# FMCio_rowsEFJK.net
KiCad netlist of a schematic drawn in Altium Designer
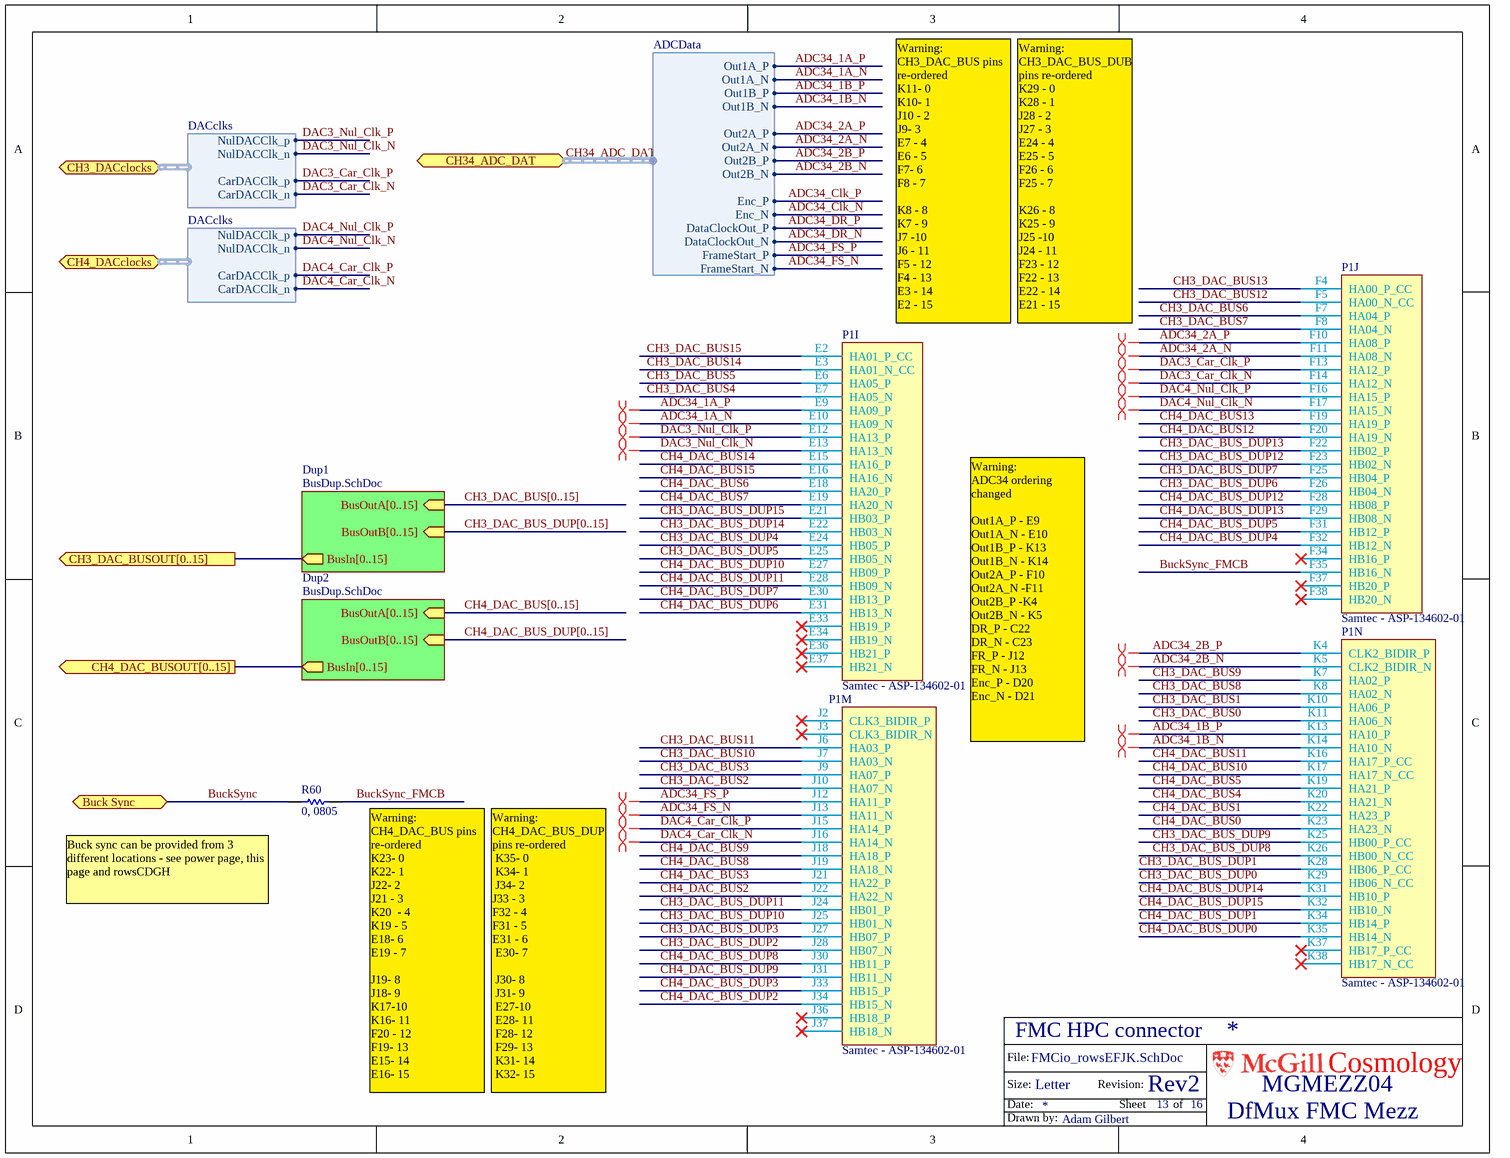
[diagram p0: FMCio_rowsEFJK.SchDoc]

(export (version "E")
  (design (tool "Eeschema 10.0.6"))
  (components
    (comp (ref "P1")
      (value "Samtec - ASP-134602-01")
      (footprint "BTB-SM1-27-2V400M")
      (description "Samtec ASP-134602-01")
      (fields (field (name "MANUFACTURER") "Samtec"))
      (libsource (lib "AdamsParts") (part "Samtec - ASP-134602-01"))
    )
    (comp (ref "R60")
      (value "0, 0805")
      (footprint "0805")
      (description "RES 0.0 OHM 1/8W 0805 SMD")
      (fields (field (name "MANUFACTURER") "e.g Vishay/Dale"))
      (libsource (lib "AdamsParts") (part "Res1812"))
    )
  )
  (nets
    (net (code "35") (name "/ADC34_1A_N") (class "Default")
      (node (ref "P1") (pin "E10") (pinfunction "HA09_N_E10") (pintype "passive"))
    )
    (net (code "36") (name "/ADC34_1A_P") (class "Default")
      (node (ref "P1") (pin "E9") (pinfunction "HA09_P_E9") (pintype "passive"))
    )
    (net (code "37") (name "/ADC34_1B_N") (class "Default")
      (node (ref "P1") (pin "K14") (pinfunction "HA10_N_K14") (pintype "passive"))
    )
    (net (code "38") (name "/ADC34_1B_P") (class "Default")
      (node (ref "P1") (pin "K13") (pinfunction "HA10_P_K13") (pintype "passive"))
    )
    (net (code "39") (name "/ADC34_2A_N") (class "Default")
      (node (ref "P1") (pin "F11") (pinfunction "HA08_N_F11") (pintype "passive"))
    )
    (net (code "40") (name "/ADC34_2A_P") (class "Default")
      (node (ref "P1") (pin "F10") (pinfunction "HA08_P_F10") (pintype "passive"))
    )
    (net (code "41") (name "/ADC34_2B_N") (class "Default")
      (node (ref "P1") (pin "K5") (pinfunction "CLK2_BIDIR_N_K5") (pintype "passive"))
    )
    (net (code "42") (name "/ADC34_2B_P") (class "Default")
      (node (ref "P1") (pin "K4") (pinfunction "CLK2_BIDIR_P_K4") (pintype "passive"))
    )
    (net (code "47") (name "/ADC34_FS_N") (class "Default")
      (node (ref "P1") (pin "J13") (pinfunction "HA11_N_J13") (pintype "passive"))
    )
    (net (code "48") (name "/ADC34_FS_P") (class "Default")
      (node (ref "P1") (pin "J12") (pinfunction "HA11_P_J12") (pintype "passive"))
    )
    (net (code "49") (name "/BuckSync") (class "Default")
      (node (ref "R60") (pin "2") (pinfunction "2_2") (pintype "passive"))
    )
    (net (code "50") (name "/BuckSync_FMCB") (class "Default")
      (node (ref "P1") (pin "F35") (pinfunction "HB16_N_F35") (pintype "passive"))
      (node (ref "R60") (pin "1") (pinfunction "1_1") (pintype "passive"))
    )
    (net (code "51") (name "/CH3_DAC_BUS0") (class "Default")
      (node (ref "P1") (pin "K11") (pinfunction "HA06_N_K11") (pintype "passive"))
    )
    (net (code "52") (name "/CH3_DAC_BUS1") (class "Default")
      (node (ref "P1") (pin "K10") (pinfunction "HA06_P_K10") (pintype "passive"))
    )
    (net (code "53") (name "/CH3_DAC_BUS2") (class "Default")
      (node (ref "P1") (pin "J10") (pinfunction "HA07_N_J10") (pintype "passive"))
    )
    (net (code "54") (name "/CH3_DAC_BUS3") (class "Default")
      (node (ref "P1") (pin "J9") (pinfunction "HA07_P_J9") (pintype "passive"))
    )
    (net (code "55") (name "/CH3_DAC_BUS4") (class "Default")
      (node (ref "P1") (pin "E7") (pinfunction "HA05_N_E7") (pintype "passive"))
    )
    (net (code "56") (name "/CH3_DAC_BUS5") (class "Default")
      (node (ref "P1") (pin "E6") (pinfunction "HA05_P_E6") (pintype "passive"))
    )
    (net (code "57") (name "/CH3_DAC_BUS6") (class "Default")
      (node (ref "P1") (pin "F7") (pinfunction "HA04_P_F7") (pintype "passive"))
    )
    (net (code "58") (name "/CH3_DAC_BUS7") (class "Default")
      (node (ref "P1") (pin "F8") (pinfunction "HA04_N_F8") (pintype "passive"))
    )
    (net (code "59") (name "/CH3_DAC_BUS8") (class "Default")
      (node (ref "P1") (pin "K8") (pinfunction "HA02_N_K8") (pintype "passive"))
    )
    (net (code "60") (name "/CH3_DAC_BUS9") (class "Default")
      (node (ref "P1") (pin "K7") (pinfunction "HA02_P_K7") (pintype "passive"))
    )
    (net (code "61") (name "/CH3_DAC_BUS10") (class "Default")
      (node (ref "P1") (pin "J7") (pinfunction "HA03_N_J7") (pintype "passive"))
    )
    (net (code "62") (name "/CH3_DAC_BUS11") (class "Default")
      (node (ref "P1") (pin "J6") (pinfunction "HA03_P_J6") (pintype "passive"))
    )
    (net (code "63") (name "/CH3_DAC_BUS12") (class "Default")
      (node (ref "P1") (pin "F5") (pinfunction "HA00_N_CC_F5") (pintype "passive"))
    )
    (net (code "64") (name "/CH3_DAC_BUS13") (class "Default")
      (node (ref "P1") (pin "F4") (pinfunction "HA00_P_CC_F4") (pintype "passive"))
    )
    (net (code "65") (name "/CH3_DAC_BUS14") (class "Default")
      (node (ref "P1") (pin "E3") (pinfunction "HA01_N_CC_E3") (pintype "passive"))
    )
    (net (code "66") (name "/CH3_DAC_BUS15") (class "Default")
      (node (ref "P1") (pin "E2") (pinfunction "HA01_P_CC_E2") (pintype "passive"))
    )
    (net (code "69") (name "/CH3_DAC_BUS_DUP0") (class "Default")
      (node (ref "P1") (pin "K29") (pinfunction "HB06_N_CC_K29") (pintype "passive"))
    )
    (net (code "70") (name "/CH3_DAC_BUS_DUP1") (class "Default")
      (node (ref "P1") (pin "K28") (pinfunction "HB06_P_CC_K28") (pintype "passive"))
    )
    (net (code "71") (name "/CH3_DAC_BUS_DUP2") (class "Default")
      (node (ref "P1") (pin "J28") (pinfunction "HB07_N_J28") (pintype "passive"))
    )
    (net (code "72") (name "/CH3_DAC_BUS_DUP3") (class "Default")
      (node (ref "P1") (pin "J27") (pinfunction "HB07_P_J27") (pintype "passive"))
    )
    (net (code "73") (name "/CH3_DAC_BUS_DUP4") (class "Default")
      (node (ref "P1") (pin "E24") (pinfunction "HB05_P_E24") (pintype "passive"))
    )
    (net (code "74") (name "/CH3_DAC_BUS_DUP5") (class "Default")
      (node (ref "P1") (pin "E25") (pinfunction "HB05_N_E25") (pintype "passive"))
    )
    (net (code "75") (name "/CH3_DAC_BUS_DUP6") (class "Default")
      (node (ref "P1") (pin "F26") (pinfunction "HB04_N_F26") (pintype "passive"))
    )
    (net (code "76") (name "/CH3_DAC_BUS_DUP7") (class "Default")
      (node (ref "P1") (pin "F25") (pinfunction "HB04_P_F25") (pintype "passive"))
    )
    (net (code "77") (name "/CH3_DAC_BUS_DUP8") (class "Default")
      (node (ref "P1") (pin "K26") (pinfunction "HB00_N_CC_K26") (pintype "passive"))
    )
    (net (code "78") (name "/CH3_DAC_BUS_DUP9") (class "Default")
      (node (ref "P1") (pin "K25") (pinfunction "HB00_P_CC_K25") (pintype "passive"))
    )
    (net (code "79") (name "/CH3_DAC_BUS_DUP10") (class "Default")
      (node (ref "P1") (pin "J25") (pinfunction "HB01_N_J25") (pintype "passive"))
    )
    (net (code "80") (name "/CH3_DAC_BUS_DUP11") (class "Default")
      (node (ref "P1") (pin "J24") (pinfunction "HB01_P_J24") (pintype "passive"))
    )
    (net (code "81") (name "/CH3_DAC_BUS_DUP12") (class "Default")
      (node (ref "P1") (pin "F23") (pinfunction "HB02_N_F23") (pintype "passive"))
    )
    (net (code "82") (name "/CH3_DAC_BUS_DUP13") (class "Default")
      (node (ref "P1") (pin "F22") (pinfunction "HB02_P_F22") (pintype "passive"))
    )
    (net (code "83") (name "/CH3_DAC_BUS_DUP14") (class "Default")
      (node (ref "P1") (pin "E22") (pinfunction "HB03_N_E22") (pintype "passive"))
    )
    (net (code "84") (name "/CH3_DAC_BUS_DUP15") (class "Default")
      (node (ref "P1") (pin "E21") (pinfunction "HB03_P_E21") (pintype "passive"))
    )
    (net (code "86") (name "/CH4_DAC_BUS0") (class "Default")
      (node (ref "P1") (pin "K23") (pinfunction "HA23_N_K23") (pintype "passive"))
    )
    (net (code "87") (name "/CH4_DAC_BUS1") (class "Default")
      (node (ref "P1") (pin "K22") (pinfunction "HA23_P_K22") (pintype "passive"))
    )
    (net (code "88") (name "/CH4_DAC_BUS2") (class "Default")
      (node (ref "P1") (pin "J22") (pinfunction "HA22_N_J22") (pintype "passive"))
    )
    (net (code "89") (name "/CH4_DAC_BUS3") (class "Default")
      (node (ref "P1") (pin "J21") (pinfunction "HA22_P_J21") (pintype "passive"))
    )
    (net (code "90") (name "/CH4_DAC_BUS4") (class "Default")
      (node (ref "P1") (pin "K20") (pinfunction "HA21_N_K20") (pintype "passive"))
    )
    (net (code "91") (name "/CH4_DAC_BUS5") (class "Default")
      (node (ref "P1") (pin "K19") (pinfunction "HA21_P_K19") (pintype "passive"))
    )
    (net (code "92") (name "/CH4_DAC_BUS6") (class "Default")
      (node (ref "P1") (pin "E18") (pinfunction "HA20_P_E18") (pintype "passive"))
    )
    (net (code "93") (name "/CH4_DAC_BUS7") (class "Default")
      (node (ref "P1") (pin "E19") (pinfunction "HA20_N_E19") (pintype "passive"))
    )
    (net (code "94") (name "/CH4_DAC_BUS8") (class "Default")
      (node (ref "P1") (pin "J19") (pinfunction "HA18_N_J19") (pintype "passive"))
    )
    (net (code "95") (name "/CH4_DAC_BUS9") (class "Default")
      (node (ref "P1") (pin "J18") (pinfunction "HA18_P_J18") (pintype "passive"))
    )
    (net (code "96") (name "/CH4_DAC_BUS10") (class "Default")
      (node (ref "P1") (pin "K17") (pinfunction "HA17_N_CC_K17") (pintype "passive"))
    )
    (net (code "97") (name "/CH4_DAC_BUS11") (class "Default")
      (node (ref "P1") (pin "K16") (pinfunction "HA17_P_CC_K16") (pintype "passive"))
    )
    (net (code "98") (name "/CH4_DAC_BUS12") (class "Default")
      (node (ref "P1") (pin "F20") (pinfunction "HA19_N_F20") (pintype "passive"))
    )
    (net (code "99") (name "/CH4_DAC_BUS13") (class "Default")
      (node (ref "P1") (pin "F19") (pinfunction "HA19_P_F19") (pintype "passive"))
    )
    (net (code "100") (name "/CH4_DAC_BUS14") (class "Default")
      (node (ref "P1") (pin "E15") (pinfunction "HA16_P_E15") (pintype "passive"))
    )
    (net (code "101") (name "/CH4_DAC_BUS15") (class "Default")
      (node (ref "P1") (pin "E16") (pinfunction "HA16_N_E16") (pintype "passive"))
    )
    (net (code "104") (name "/CH4_DAC_BUS_DUP0") (class "Default")
      (node (ref "P1") (pin "K35") (pinfunction "HB14_N_K35") (pintype "passive"))
    )
    (net (code "105") (name "/CH4_DAC_BUS_DUP1") (class "Default")
      (node (ref "P1") (pin "K34") (pinfunction "HB14_P_K34") (pintype "passive"))
    )
    (net (code "106") (name "/CH4_DAC_BUS_DUP2") (class "Default")
      (node (ref "P1") (pin "J34") (pinfunction "HB15_N_J34") (pintype "passive"))
    )
    (net (code "107") (name "/CH4_DAC_BUS_DUP3") (class "Default")
      (node (ref "P1") (pin "J33") (pinfunction "HB15_P_J33") (pintype "passive"))
    )
    (net (code "108") (name "/CH4_DAC_BUS_DUP4") (class "Default")
      (node (ref "P1") (pin "F32") (pinfunction "HB12_N_F32") (pintype "passive"))
    )
    (net (code "109") (name "/CH4_DAC_BUS_DUP5") (class "Default")
      (node (ref "P1") (pin "F31") (pinfunction "HB12_P_F31") (pintype "passive"))
    )
    (net (code "110") (name "/CH4_DAC_BUS_DUP6") (class "Default")
      (node (ref "P1") (pin "E31") (pinfunction "HB13_N_E31") (pintype "passive"))
    )
    (net (code "111") (name "/CH4_DAC_BUS_DUP7") (class "Default")
      (node (ref "P1") (pin "E30") (pinfunction "HB13_P_E30") (pintype "passive"))
    )
    (net (code "112") (name "/CH4_DAC_BUS_DUP8") (class "Default")
      (node (ref "P1") (pin "J30") (pinfunction "HB11_P_J30") (pintype "passive"))
    )
    (net (code "113") (name "/CH4_DAC_BUS_DUP9") (class "Default")
      (node (ref "P1") (pin "J31") (pinfunction "HB11_N_J31") (pintype "passive"))
    )
    (net (code "114") (name "/CH4_DAC_BUS_DUP10") (class "Default")
      (node (ref "P1") (pin "E27") (pinfunction "HB09_P_E27") (pintype "passive"))
    )
    (net (code "115") (name "/CH4_DAC_BUS_DUP11") (class "Default")
      (node (ref "P1") (pin "E28") (pinfunction "HB09_N_E28") (pintype "passive"))
    )
    (net (code "116") (name "/CH4_DAC_BUS_DUP12") (class "Default")
      (node (ref "P1") (pin "F28") (pinfunction "HB08_P_F28") (pintype "passive"))
    )
    (net (code "117") (name "/CH4_DAC_BUS_DUP13") (class "Default")
      (node (ref "P1") (pin "F29") (pinfunction "HB08_N_F29") (pintype "passive"))
    )
    (net (code "118") (name "/CH4_DAC_BUS_DUP14") (class "Default")
      (node (ref "P1") (pin "K31") (pinfunction "HB10_P_K31") (pintype "passive"))
    )
    (net (code "119") (name "/CH4_DAC_BUS_DUP15") (class "Default")
      (node (ref "P1") (pin "K32") (pinfunction "HB10_N_K32") (pintype "passive"))
    )
    (net (code "122") (name "/DAC3_Car_Clk_N") (class "Default")
      (node (ref "P1") (pin "F14") (pinfunction "HA12_N_F14") (pintype "passive"))
    )
    (net (code "123") (name "/DAC3_Car_Clk_P") (class "Default")
      (node (ref "P1") (pin "F13") (pinfunction "HA12_P_F13") (pintype "passive"))
    )
    (net (code "124") (name "/DAC3_Nul_Clk_N") (class "Default")
      (node (ref "P1") (pin "E13") (pinfunction "HA13_N_E13") (pintype "passive"))
    )
    (net (code "125") (name "/DAC3_Nul_Clk_P") (class "Default")
      (node (ref "P1") (pin "E12") (pinfunction "HA13_P_E12") (pintype "passive"))
    )
    (net (code "126") (name "/DAC4_Car_Clk_N") (class "Default")
      (node (ref "P1") (pin "J16") (pinfunction "HA14_N_J16") (pintype "passive"))
    )
    (net (code "127") (name "/DAC4_Car_Clk_P") (class "Default")
      (node (ref "P1") (pin "J15") (pinfunction "HA14_P_J15") (pintype "passive"))
    )
    (net (code "128") (name "/DAC4_Nul_Clk_N") (class "Default")
      (node (ref "P1") (pin "F17") (pinfunction "HA15_N_F17") (pintype "passive"))
    )
    (net (code "129") (name "/DAC4_Nul_Clk_P") (class "Default")
      (node (ref "P1") (pin "F16") (pinfunction "HA15_P_F16") (pintype "passive"))
    )
    (net (code "131") (name "unconnected-(P1I-HB19_N-PadE34)") (class "Default")
      (node (ref "P1") (pin "E34") (pinfunction "HB19_N_E34") (pintype "passive+no_connect"))
    )
    (net (code "132") (name "unconnected-(P1I-HB19_P-PadE33)") (class "Default")
      (node (ref "P1") (pin "E33") (pinfunction "HB19_P_E33") (pintype "passive+no_connect"))
    )
    (net (code "133") (name "unconnected-(P1I-HB21_N-PadE37)") (class "Default")
      (node (ref "P1") (pin "E37") (pinfunction "HB21_N_E37") (pintype "passive+no_connect"))
    )
    (net (code "134") (name "unconnected-(P1I-HB21_P-PadE36)") (class "Default")
      (node (ref "P1") (pin "E36") (pinfunction "HB21_P_E36") (pintype "passive+no_connect"))
    )
    (net (code "135") (name "unconnected-(P1J-HB16_P-PadF34)") (class "Default")
      (node (ref "P1") (pin "F34") (pinfunction "HB16_P_F34") (pintype "passive+no_connect"))
    )
    (net (code "136") (name "unconnected-(P1J-HB20_N-PadF38)") (class "Default")
      (node (ref "P1") (pin "F38") (pinfunction "HB20_N_F38") (pintype "passive+no_connect"))
    )
    (net (code "137") (name "unconnected-(P1J-HB20_P-PadF37)") (class "Default")
      (node (ref "P1") (pin "F37") (pinfunction "HB20_P_F37") (pintype "passive+no_connect"))
    )
    (net (code "138") (name "unconnected-(P1M-CLK3_BIDIR_N-PadJ3)") (class "Default")
      (node (ref "P1") (pin "J3") (pinfunction "CLK3_BIDIR_N_J3") (pintype "passive+no_connect"))
    )
    (net (code "139") (name "unconnected-(P1M-CLK3_BIDIR_P-PadJ2)") (class "Default")
      (node (ref "P1") (pin "J2") (pinfunction "CLK3_BIDIR_P_J2") (pintype "passive+no_connect"))
    )
    (net (code "140") (name "unconnected-(P1M-HB18_N-PadJ37)") (class "Default")
      (node (ref "P1") (pin "J37") (pinfunction "HB18_N_J37") (pintype "passive+no_connect"))
    )
    (net (code "141") (name "unconnected-(P1M-HB18_P-PadJ36)") (class "Default")
      (node (ref "P1") (pin "J36") (pinfunction "HB18_P_J36") (pintype "passive+no_connect"))
    )
    (net (code "142") (name "unconnected-(P1N-HB17_N_CC-PadK38)") (class "Default")
      (node (ref "P1") (pin "K38") (pinfunction "HB17_N_CC_K38") (pintype "passive+no_connect"))
    )
    (net (code "143") (name "unconnected-(P1N-HB17_P_CC-PadK37)") (class "Default")
      (node (ref "P1") (pin "K37") (pinfunction "HB17_P_CC_K37") (pintype "passive+no_connect"))
    )
  )
)
